# TempestShockerUpper.net
KiCad netlist of a schematic drawn in EAGLE
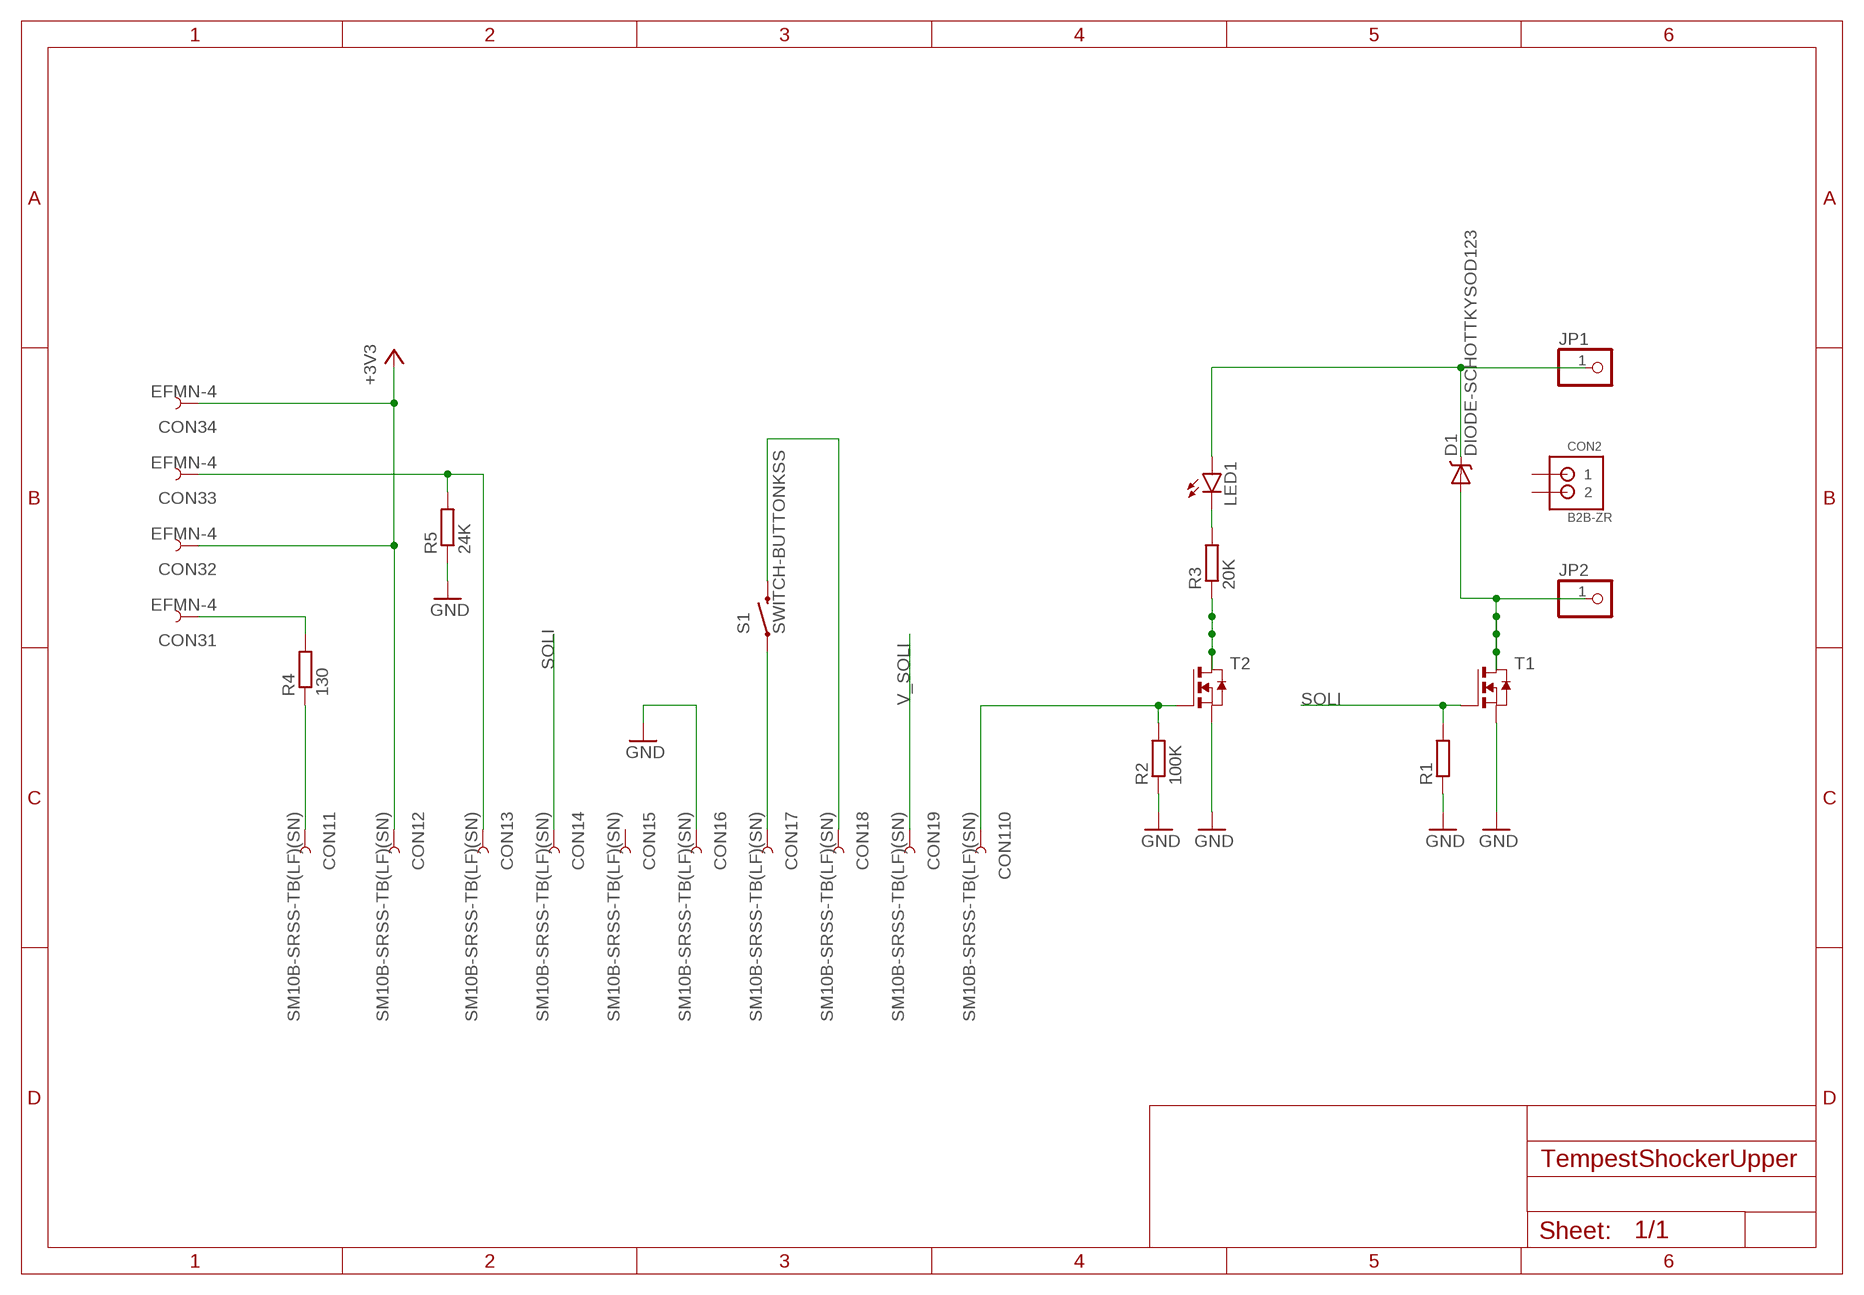
[diagram p0: schematic, sheet 1]

(export (version "E")
  (design (tool "Eeschema 10.0.6"))
  (components
    (comp (ref "CON1")
      (value "SM10B-SRSS-TB(LF)(SN)")
      (footprint "eagle-import:SM10B-SRSS-TB")
      (libsource (lib "eagle-import") (part "SM10B-SRSS-TB(LF)(SN)"))
    )
    (comp (ref "CON2")
      (value "B2B-ZR")
      (footprint "eagle-import:S2B-ZR")
      (libsource (lib "eagle-import") (part "B2B-ZR"))
    )
    (comp (ref "CON3")
      (value "EFMN-4")
      (footprint "eagle-import:EFMN-4")
      (libsource (lib "eagle-import") (part "EFMN-4"))
    )
    (comp (ref "D1")
      (value "DIODE-SCHOTTKYSOD123")
      (footprint "eagle-import:SOD123")
      (libsource (lib "eagle-import") (part "DIODE-SCHOTTKYSOD123"))
    )
    (comp (ref "JP1")
      (value "PINHD-1X1")
      (footprint "eagle-import:1X01")
      (libsource (lib "eagle-import") (part "PINHD-1X1"))
    )
    (comp (ref "JP2")
      (value "PINHD-1X1")
      (footprint "eagle-import:1X01")
      (libsource (lib "eagle-import") (part "PINHD-1X1"))
    )
    (comp (ref "LED1")
      (value "LED0603")
      (footprint "eagle-import:LED-0603")
      (libsource (lib "eagle-import") (part "LED0603"))
    )
    (comp (ref "R1")
      (value "R0603")
      (footprint "eagle-import:_0603MP")
      (libsource (lib "eagle-import") (part "R0603"))
    )
    (comp (ref "R2")
      (value "100K")
      (footprint "eagle-import:_0603MP")
      (libsource (lib "eagle-import") (part "R0603"))
    )
    (comp (ref "R3")
      (value "20K")
      (footprint "eagle-import:_0603MP")
      (libsource (lib "eagle-import") (part "R0603"))
    )
    (comp (ref "R4")
      (value "130")
      (footprint "eagle-import:_0603MP")
      (libsource (lib "eagle-import") (part "R0603"))
    )
    (comp (ref "R5")
      (value "24K")
      (footprint "eagle-import:_0603MP")
      (libsource (lib "eagle-import") (part "R0603"))
    )
    (comp (ref "S1")
      (value "SWITCH-BUTTONKSS")
      (footprint "eagle-import:KSS")
      (libsource (lib "eagle-import") (part "SWITCH-BUTTONKSS"))
    )
    (comp (ref "T1")
      (value "NMOSSOT23-6")
      (footprint "eagle-import:SOT23-6")
      (libsource (lib "eagle-import") (part "NMOSSOT23-6"))
    )
    (comp (ref "T2")
      (value "NMOSSOT23-6")
      (footprint "eagle-import:SOT23-6")
      (libsource (lib "eagle-import") (part "NMOSSOT23-6"))
    )
  )
  (nets
    (net (code "1") (name "+3V3") (class "Default")
      (node (ref "CON1") (pin "2") (pinfunction "1_2") (pintype "bidirectional"))
      (node (ref "CON3") (pin "2") (pinfunction "1_2") (pintype "bidirectional"))
      (node (ref "CON3") (pin "4") (pinfunction "1_4") (pintype "bidirectional"))
    )
    (net (code "2") (name "/SOLI") (class "Default")
      (node (ref "CON1") (pin "4") (pinfunction "1_4") (pintype "bidirectional"))
      (node (ref "R1") (pin "2") (pinfunction "2_2") (pintype "passive"))
      (node (ref "T1") (pin "3") (pinfunction "G_3") (pintype "passive"))
    )
    (net (code "3") (name "/V_SOLI") (class "Default")
      (node (ref "CON1") (pin "9") (pinfunction "1_9") (pintype "bidirectional"))
      (node (ref "D1") (pin "C") (pinfunction "C_C") (pintype "passive"))
      (node (ref "JP1") (pin "1") (pinfunction "1_1") (pintype "passive"))
      (node (ref "LED1") (pin "A") (pinfunction "A_A") (pintype "passive"))
    )
    (net (code "4") (name "GND") (class "Default")
      (node (ref "CON1") (pin "6") (pinfunction "1_6") (pintype "bidirectional"))
      (node (ref "R1") (pin "1") (pinfunction "1_1") (pintype "passive"))
      (node (ref "R2") (pin "1") (pinfunction "1_1") (pintype "passive"))
      (node (ref "R5") (pin "1") (pinfunction "1_1") (pintype "passive"))
      (node (ref "T1") (pin "4") (pinfunction "S_4") (pintype "passive"))
      (node (ref "T2") (pin "4") (pinfunction "S_4") (pintype "passive"))
    )
    (net (code "5") (name "Net-(CON1-Pad1)") (class "Default")
      (node (ref "CON1") (pin "1") (pinfunction "1_1") (pintype "bidirectional"))
      (node (ref "R4") (pin "1") (pinfunction "1_1") (pintype "passive"))
    )
    (net (code "6") (name "Net-(CON1B-1)") (class "Default")
      (node (ref "CON1") (pin "10") (pinfunction "1_10") (pintype "bidirectional"))
      (node (ref "R2") (pin "2") (pinfunction "2_2") (pintype "passive"))
      (node (ref "T2") (pin "3") (pinfunction "G_3") (pintype "passive"))
    )
    (net (code "7") (name "Net-(CON1D-1)") (class "Default")
      (node (ref "CON1") (pin "3") (pinfunction "1_3") (pintype "bidirectional"))
      (node (ref "CON3") (pin "3") (pinfunction "1_3") (pintype "bidirectional"))
      (node (ref "R5") (pin "2") (pinfunction "2_2") (pintype "passive"))
    )
    (net (code "8") (name "Net-(CON1H-1)") (class "Default")
      (node (ref "CON1") (pin "7") (pinfunction "1_7") (pintype "bidirectional"))
      (node (ref "S1") (pin "1") (pinfunction "1_1") (pintype "passive"))
    )
    (net (code "9") (name "Net-(CON1I-1)") (class "Default")
      (node (ref "CON1") (pin "8") (pinfunction "1_8") (pintype "bidirectional"))
      (node (ref "S1") (pin "2") (pinfunction "2_2") (pintype "passive"))
    )
    (net (code "10") (name "Net-(CON3-Pad1)") (class "Default")
      (node (ref "CON3") (pin "1") (pinfunction "1_1") (pintype "bidirectional"))
      (node (ref "R4") (pin "2") (pinfunction "2_2") (pintype "passive"))
    )
    (net (code "11") (name "Net-(LED1-PadC)") (class "Default")
      (node (ref "LED1") (pin "C") (pinfunction "C_C") (pintype "passive"))
      (node (ref "R3") (pin "2") (pinfunction "2_2") (pintype "passive"))
    )
    (net (code "12") (name "Net-(T1-D)") (class "Default")
      (node (ref "D1") (pin "A") (pinfunction "A_A") (pintype "passive"))
      (node (ref "JP2") (pin "1") (pinfunction "1_1") (pintype "passive"))
      (node (ref "T1") (pin "1") (pinfunction "D_1") (pintype "passive"))
      (node (ref "T1") (pin "2") (pinfunction "D1_2") (pintype "passive"))
      (node (ref "T1") (pin "5") (pinfunction "D2_5") (pintype "passive"))
      (node (ref "T1") (pin "6") (pinfunction "D3_6") (pintype "passive"))
    )
    (net (code "13") (name "Net-(T2-D)") (class "Default")
      (node (ref "R3") (pin "1") (pinfunction "1_1") (pintype "passive"))
      (node (ref "T2") (pin "1") (pinfunction "D_1") (pintype "passive"))
      (node (ref "T2") (pin "2") (pinfunction "D1_2") (pintype "passive"))
      (node (ref "T2") (pin "5") (pinfunction "D2_5") (pintype "passive"))
      (node (ref "T2") (pin "6") (pinfunction "D3_6") (pintype "passive"))
    )
    (net (code "14") (name "unconnected-(CON1F-1-Pad5)") (class "Default")
      (node (ref "CON1") (pin "5") (pinfunction "1_5") (pintype "bidirectional"))
    )
    (net (code "15") (name "unconnected-(CON2-Pad1)") (class "Default")
      (node (ref "CON2") (pin "1") (pinfunction "1_1") (pintype "bidirectional"))
    )
    (net (code "16") (name "unconnected-(CON2-Pad2)") (class "Default")
      (node (ref "CON2") (pin "2") (pinfunction "2_2") (pintype "bidirectional"))
    )
  )
)
